# NE602-Upconverter.net
KiCad netlist of a schematic drawn in EAGLE
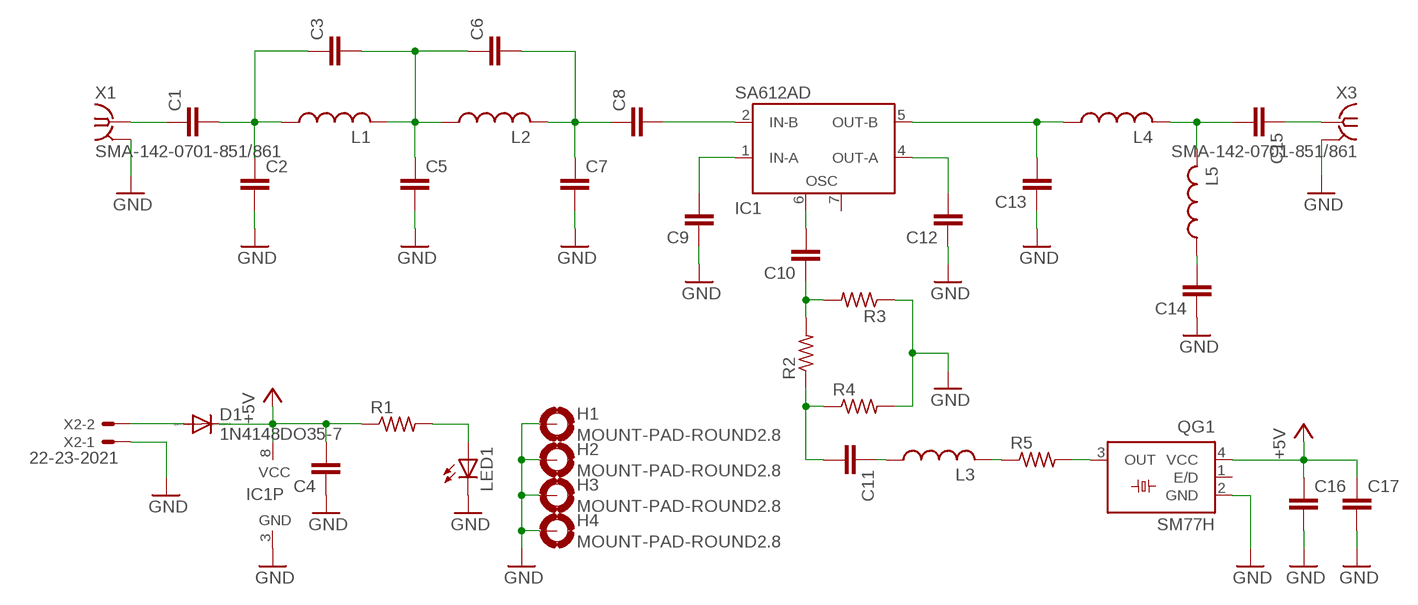
[diagram p0: schematic, sheet 1]

(export (version "E")
  (design (tool "Eeschema 10.0.6"))
  (components
    (comp (ref "C1")
      (value "C-EUC1206")
      (footprint "eagle-import:C1206")
      (libsource (lib "eagle-import") (part "C-EUC1206"))
    )
    (comp (ref "C2")
      (value "C-EUC1206")
      (footprint "eagle-import:C1206")
      (libsource (lib "eagle-import") (part "C-EUC1206"))
    )
    (comp (ref "C3")
      (value "C-EUC1206")
      (footprint "eagle-import:C1206")
      (libsource (lib "eagle-import") (part "C-EUC1206"))
    )
    (comp (ref "C4")
      (value "C-EUC1206")
      (footprint "eagle-import:C1206")
      (libsource (lib "eagle-import") (part "C-EUC1206"))
    )
    (comp (ref "C5")
      (value "C-EUC1206")
      (footprint "eagle-import:C1206")
      (libsource (lib "eagle-import") (part "C-EUC1206"))
    )
    (comp (ref "C6")
      (value "C-EUC1206")
      (footprint "eagle-import:C1206")
      (libsource (lib "eagle-import") (part "C-EUC1206"))
    )
    (comp (ref "C7")
      (value "C-EUC1206")
      (footprint "eagle-import:C1206")
      (libsource (lib "eagle-import") (part "C-EUC1206"))
    )
    (comp (ref "C8")
      (value "C-EUC1206")
      (footprint "eagle-import:C1206")
      (libsource (lib "eagle-import") (part "C-EUC1206"))
    )
    (comp (ref "C9")
      (value "C-EUC1206")
      (footprint "eagle-import:C1206")
      (libsource (lib "eagle-import") (part "C-EUC1206"))
    )
    (comp (ref "C10")
      (value "C-EUC1206")
      (footprint "eagle-import:C1206")
      (libsource (lib "eagle-import") (part "C-EUC1206"))
    )
    (comp (ref "C11")
      (value "C-EUC1206")
      (footprint "eagle-import:C1206")
      (libsource (lib "eagle-import") (part "C-EUC1206"))
    )
    (comp (ref "C12")
      (value "C-EUC1206")
      (footprint "eagle-import:C1206")
      (libsource (lib "eagle-import") (part "C-EUC1206"))
    )
    (comp (ref "C13")
      (value "C-EUC1206")
      (footprint "eagle-import:C1206")
      (libsource (lib "eagle-import") (part "C-EUC1206"))
    )
    (comp (ref "C14")
      (value "C-EUC1206")
      (footprint "eagle-import:C1206")
      (libsource (lib "eagle-import") (part "C-EUC1206"))
    )
    (comp (ref "C15")
      (value "C-EUC1206")
      (footprint "eagle-import:C1206")
      (libsource (lib "eagle-import") (part "C-EUC1206"))
    )
    (comp (ref "C16")
      (value "C-EUC1206")
      (footprint "eagle-import:C1206")
      (libsource (lib "eagle-import") (part "C-EUC1206"))
    )
    (comp (ref "C17")
      (value "C-EUC1206")
      (footprint "eagle-import:C1206")
      (libsource (lib "eagle-import") (part "C-EUC1206"))
    )
    (comp (ref "D1")
      (value "1N4148DO35-7")
      (footprint "eagle-import:DO35-7")
      (libsource (lib "eagle-import") (part "1N4148DO35-7"))
    )
    (comp (ref "H1")
      (value "MOUNT-PAD-ROUND2.8")
      (footprint "eagle-import:2,8-PAD")
      (libsource (lib "eagle-import") (part "MOUNT-PAD-ROUND2.8"))
    )
    (comp (ref "H2")
      (value "MOUNT-PAD-ROUND2.8")
      (footprint "eagle-import:2,8-PAD")
      (libsource (lib "eagle-import") (part "MOUNT-PAD-ROUND2.8"))
    )
    (comp (ref "H3")
      (value "MOUNT-PAD-ROUND2.8")
      (footprint "eagle-import:2,8-PAD")
      (libsource (lib "eagle-import") (part "MOUNT-PAD-ROUND2.8"))
    )
    (comp (ref "H4")
      (value "MOUNT-PAD-ROUND2.8")
      (footprint "eagle-import:2,8-PAD")
      (libsource (lib "eagle-import") (part "MOUNT-PAD-ROUND2.8"))
    )
    (comp (ref "IC1")
      (value "SA612AD")
      (footprint "eagle-import:SO08")
      (libsource (lib "eagle-import") (part "SA612AD"))
    )
    (comp (ref "L1")
      (value "L-USL3225M")
      (footprint "eagle-import:L3225M")
      (libsource (lib "eagle-import") (part "L-USL3225M"))
    )
    (comp (ref "L2")
      (value "L-USL3225M")
      (footprint "eagle-import:L3225M")
      (libsource (lib "eagle-import") (part "L-USL3225M"))
    )
    (comp (ref "L3")
      (value "L-USL3225M")
      (footprint "eagle-import:L3225M")
      (libsource (lib "eagle-import") (part "L-USL3225M"))
    )
    (comp (ref "L4")
      (value "L-USL3225M")
      (footprint "eagle-import:L3225M")
      (libsource (lib "eagle-import") (part "L-USL3225M"))
    )
    (comp (ref "L5")
      (value "L-USL3225M")
      (footprint "eagle-import:L3225M")
      (libsource (lib "eagle-import") (part "L-USL3225M"))
    )
    (comp (ref "LED1")
      (value "LED3MM")
      (footprint "eagle-import:LED3MM")
      (libsource (lib "eagle-import") (part "LED3MM"))
    )
    (comp (ref "QG1")
      (value "SM77H")
      (footprint "eagle-import:SM77H")
      (libsource (lib "eagle-import") (part "SM77H"))
    )
    (comp (ref "R1")
      (value "R-US_M1206")
      (footprint "eagle-import:M1206")
      (libsource (lib "eagle-import") (part "R-US_M1206"))
    )
    (comp (ref "R2")
      (value "R-US_M1206")
      (footprint "eagle-import:M1206")
      (libsource (lib "eagle-import") (part "R-US_M1206"))
    )
    (comp (ref "R3")
      (value "R-US_M1206")
      (footprint "eagle-import:M1206")
      (libsource (lib "eagle-import") (part "R-US_M1206"))
    )
    (comp (ref "R4")
      (value "R-US_M1206")
      (footprint "eagle-import:M1206")
      (libsource (lib "eagle-import") (part "R-US_M1206"))
    )
    (comp (ref "R5")
      (value "R-US_M1206")
      (footprint "eagle-import:M1206")
      (libsource (lib "eagle-import") (part "R-US_M1206"))
    )
    (comp (ref "X1")
      (value "SMA-142-0701-851/861")
      (footprint "eagle-import:J502-ND-142-0701-851_861")
      (fields (field (name "MF") "JOHNSON COMPONENTS") (field (name "MPN") "142-0701-851"))
      (libsource (lib "eagle-import") (part "SMA-142-0701-851/861"))
    )
    (comp (ref "X2")
      (value "22-23-2021")
      (footprint "eagle-import:22-23-2021")
      (fields (field (name "MF") "MOLEX"))
      (libsource (lib "eagle-import") (part "22-23-2021"))
    )
    (comp (ref "X3")
      (value "SMA-142-0701-851/861")
      (footprint "eagle-import:J502-ND-142-0701-851_861")
      (fields (field (name "MF") "JOHNSON COMPONENTS") (field (name "MPN") "142-0701-851"))
      (libsource (lib "eagle-import") (part "SMA-142-0701-851/861"))
    )
  )
  (nets
    (net (code "1") (name "+5V") (class "Default")
      (node (ref "C16") (pin "1") (pinfunction "1_1") (pintype "passive"))
      (node (ref "C17") (pin "1") (pinfunction "1_1") (pintype "passive"))
      (node (ref "C4") (pin "2") (pinfunction "2_2") (pintype "passive"))
      (node (ref "D1") (pin "C") (pinfunction "C_C") (pintype "passive"))
      (node (ref "IC1") (pin "8") (pinfunction "VCC_8") (pintype "power_in"))
      (node (ref "QG1") (pin "4") (pinfunction "VCC_4") (pintype "power_in"))
      (node (ref "R1") (pin "1") (pinfunction "1_1") (pintype "passive"))
    )
    (net (code "2") (name "GND") (class "Default")
      (node (ref "C12") (pin "1") (pinfunction "1_1") (pintype "passive"))
      (node (ref "C13") (pin "1") (pinfunction "1_1") (pintype "passive"))
      (node (ref "C14") (pin "1") (pinfunction "1_1") (pintype "passive"))
      (node (ref "C16") (pin "2") (pinfunction "2_2") (pintype "passive"))
      (node (ref "C17") (pin "2") (pinfunction "2_2") (pintype "passive"))
      (node (ref "C2") (pin "2") (pinfunction "2_2") (pintype "passive"))
      (node (ref "C4") (pin "1") (pinfunction "1_1") (pintype "passive"))
      (node (ref "C5") (pin "2") (pinfunction "2_2") (pintype "passive"))
      (node (ref "C7") (pin "2") (pinfunction "2_2") (pintype "passive"))
      (node (ref "C9") (pin "1") (pinfunction "1_1") (pintype "passive"))
      (node (ref "H1") (pin "B2,8") (pinfunction "MOUNT_B2,8") (pintype "passive"))
      (node (ref "H2") (pin "B2,8") (pinfunction "MOUNT_B2,8") (pintype "passive"))
      (node (ref "H3") (pin "B2,8") (pinfunction "MOUNT_B2,8") (pintype "passive"))
      (node (ref "H4") (pin "B2,8") (pinfunction "MOUNT_B2,8") (pintype "passive"))
      (node (ref "IC1") (pin "3") (pinfunction "GND_3") (pintype "power_in"))
      (node (ref "LED1") (pin "K") (pinfunction "C_K") (pintype "passive"))
      (node (ref "QG1") (pin "2") (pinfunction "GND_2") (pintype "power_in"))
      (node (ref "R3") (pin "1") (pinfunction "1_1") (pintype "passive"))
      (node (ref "R4") (pin "2") (pinfunction "2_2") (pintype "passive"))
      (node (ref "X1") (pin "G@1") (pinfunction "2_G@1") (pintype "passive"))
      (node (ref "X1") (pin "G@2") (pinfunction "2_G@2") (pintype "passive"))
      (node (ref "X1") (pin "G@3") (pinfunction "2_G@3") (pintype "passive"))
      (node (ref "X1") (pin "G@4") (pinfunction "2_G@4") (pintype "passive"))
      (node (ref "X2") (pin "1") (pinfunction "S_1") (pintype "passive"))
      (node (ref "X3") (pin "G@1") (pinfunction "2_G@1") (pintype "passive"))
      (node (ref "X3") (pin "G@2") (pinfunction "2_G@2") (pintype "passive"))
      (node (ref "X3") (pin "G@3") (pinfunction "2_G@3") (pintype "passive"))
      (node (ref "X3") (pin "G@4") (pinfunction "2_G@4") (pintype "passive"))
    )
    (net (code "3") (name "Net-(C1-Pad1)") (class "Default")
      (node (ref "C1") (pin "1") (pinfunction "1_1") (pintype "passive"))
      (node (ref "X1") (pin "1") (pinfunction "1_1") (pintype "passive"))
    )
    (net (code "4") (name "Net-(C1-Pad2)") (class "Default")
      (node (ref "C1") (pin "2") (pinfunction "2_2") (pintype "passive"))
      (node (ref "C2") (pin "1") (pinfunction "1_1") (pintype "passive"))
      (node (ref "C3") (pin "1") (pinfunction "1_1") (pintype "passive"))
      (node (ref "L1") (pin "1") (pinfunction "1_1") (pintype "passive"))
    )
    (net (code "5") (name "Net-(C3-Pad2)") (class "Default")
      (node (ref "C3") (pin "2") (pinfunction "2_2") (pintype "passive"))
      (node (ref "C5") (pin "1") (pinfunction "1_1") (pintype "passive"))
      (node (ref "C6") (pin "1") (pinfunction "1_1") (pintype "passive"))
      (node (ref "L1") (pin "2") (pinfunction "2_2") (pintype "passive"))
      (node (ref "L2") (pin "1") (pinfunction "1_1") (pintype "passive"))
    )
    (net (code "6") (name "Net-(C6-Pad2)") (class "Default")
      (node (ref "C6") (pin "2") (pinfunction "2_2") (pintype "passive"))
      (node (ref "C7") (pin "1") (pinfunction "1_1") (pintype "passive"))
      (node (ref "C8") (pin "1") (pinfunction "1_1") (pintype "passive"))
      (node (ref "L2") (pin "2") (pinfunction "2_2") (pintype "passive"))
    )
    (net (code "7") (name "Net-(C10-Pad1)") (class "Default")
      (node (ref "C10") (pin "1") (pinfunction "1_1") (pintype "passive"))
      (node (ref "R2") (pin "2") (pinfunction "2_2") (pintype "passive"))
      (node (ref "R3") (pin "2") (pinfunction "2_2") (pintype "passive"))
    )
    (net (code "8") (name "Net-(C11-Pad1)") (class "Default")
      (node (ref "C11") (pin "1") (pinfunction "1_1") (pintype "passive"))
      (node (ref "L3") (pin "1") (pinfunction "1_1") (pintype "passive"))
    )
    (net (code "9") (name "Net-(C11-Pad2)") (class "Default")
      (node (ref "C11") (pin "2") (pinfunction "2_2") (pintype "passive"))
      (node (ref "R2") (pin "1") (pinfunction "1_1") (pintype "passive"))
      (node (ref "R4") (pin "1") (pinfunction "1_1") (pintype "passive"))
    )
    (net (code "10") (name "Net-(C14-Pad2)") (class "Default")
      (node (ref "C14") (pin "2") (pinfunction "2_2") (pintype "passive"))
      (node (ref "L5") (pin "1") (pinfunction "1_1") (pintype "passive"))
    )
    (net (code "11") (name "Net-(C15-Pad1)") (class "Default")
      (node (ref "C15") (pin "1") (pinfunction "1_1") (pintype "passive"))
      (node (ref "X3") (pin "1") (pinfunction "1_1") (pintype "passive"))
    )
    (net (code "12") (name "Net-(C15-Pad2)") (class "Default")
      (node (ref "C15") (pin "2") (pinfunction "2_2") (pintype "passive"))
      (node (ref "L4") (pin "2") (pinfunction "2_2") (pintype "passive"))
      (node (ref "L5") (pin "2") (pinfunction "2_2") (pintype "passive"))
    )
    (net (code "13") (name "Net-(IC1A-IN-A)") (class "Default")
      (node (ref "C9") (pin "2") (pinfunction "2_2") (pintype "passive"))
      (node (ref "IC1") (pin "1") (pinfunction "IN-A_1") (pintype "input"))
    )
    (net (code "14") (name "Net-(IC1A-IN-B)") (class "Default")
      (node (ref "C8") (pin "2") (pinfunction "2_2") (pintype "passive"))
      (node (ref "IC1") (pin "2") (pinfunction "IN-B_2") (pintype "input"))
    )
    (net (code "15") (name "Net-(IC1A-OSC)") (class "Default")
      (node (ref "C10") (pin "2") (pinfunction "2_2") (pintype "passive"))
      (node (ref "IC1") (pin "6") (pinfunction "OSC_6") (pintype "passive"))
    )
    (net (code "16") (name "Net-(IC1A-OUT-A)") (class "Default")
      (node (ref "C12") (pin "2") (pinfunction "2_2") (pintype "passive"))
      (node (ref "IC1") (pin "4") (pinfunction "OUT-A_4") (pintype "input"))
    )
    (net (code "17") (name "Net-(IC1A-OUT-B)") (class "Default")
      (node (ref "C13") (pin "2") (pinfunction "2_2") (pintype "passive"))
      (node (ref "IC1") (pin "5") (pinfunction "OUT-B_5") (pintype "input"))
      (node (ref "L4") (pin "1") (pinfunction "1_1") (pintype "passive"))
    )
    (net (code "18") (name "Net-(L3-Pad2)") (class "Default")
      (node (ref "L3") (pin "2") (pinfunction "2_2") (pintype "passive"))
      (node (ref "R5") (pin "1") (pinfunction "1_1") (pintype "passive"))
    )
    (net (code "19") (name "Net-(LED1-PadA)") (class "Default")
      (node (ref "LED1") (pin "A") (pinfunction "A_A") (pintype "passive"))
      (node (ref "R1") (pin "2") (pinfunction "2_2") (pintype "passive"))
    )
    (net (code "20") (name "Net-(QG1-OUT)") (class "Default")
      (node (ref "QG1") (pin "3") (pinfunction "OUT_3") (pintype "output"))
      (node (ref "R5") (pin "2") (pinfunction "2_2") (pintype "passive"))
    )
    (net (code "21") (name "Net-(X2B-S)") (class "Default")
      (node (ref "D1") (pin "A") (pinfunction "A_A") (pintype "passive"))
      (node (ref "X2") (pin "2") (pinfunction "S_2") (pintype "passive"))
    )
    (net (code "22") (name "unconnected-(IC1A-OSC'-Pad7)") (class "Default")
      (node (ref "IC1") (pin "7") (pinfunction "OSC'_7") (pintype "passive"))
    )
    (net (code "23") (name "unconnected-(QG1-E{slash}D-Pad1)") (class "Default")
      (node (ref "QG1") (pin "1") (pinfunction "E/D_1") (pintype "input"))
    )
  )
)
